# SimpleSwitchPirLightCO2Orig.net
KiCad netlist of a schematic drawn in EAGLE
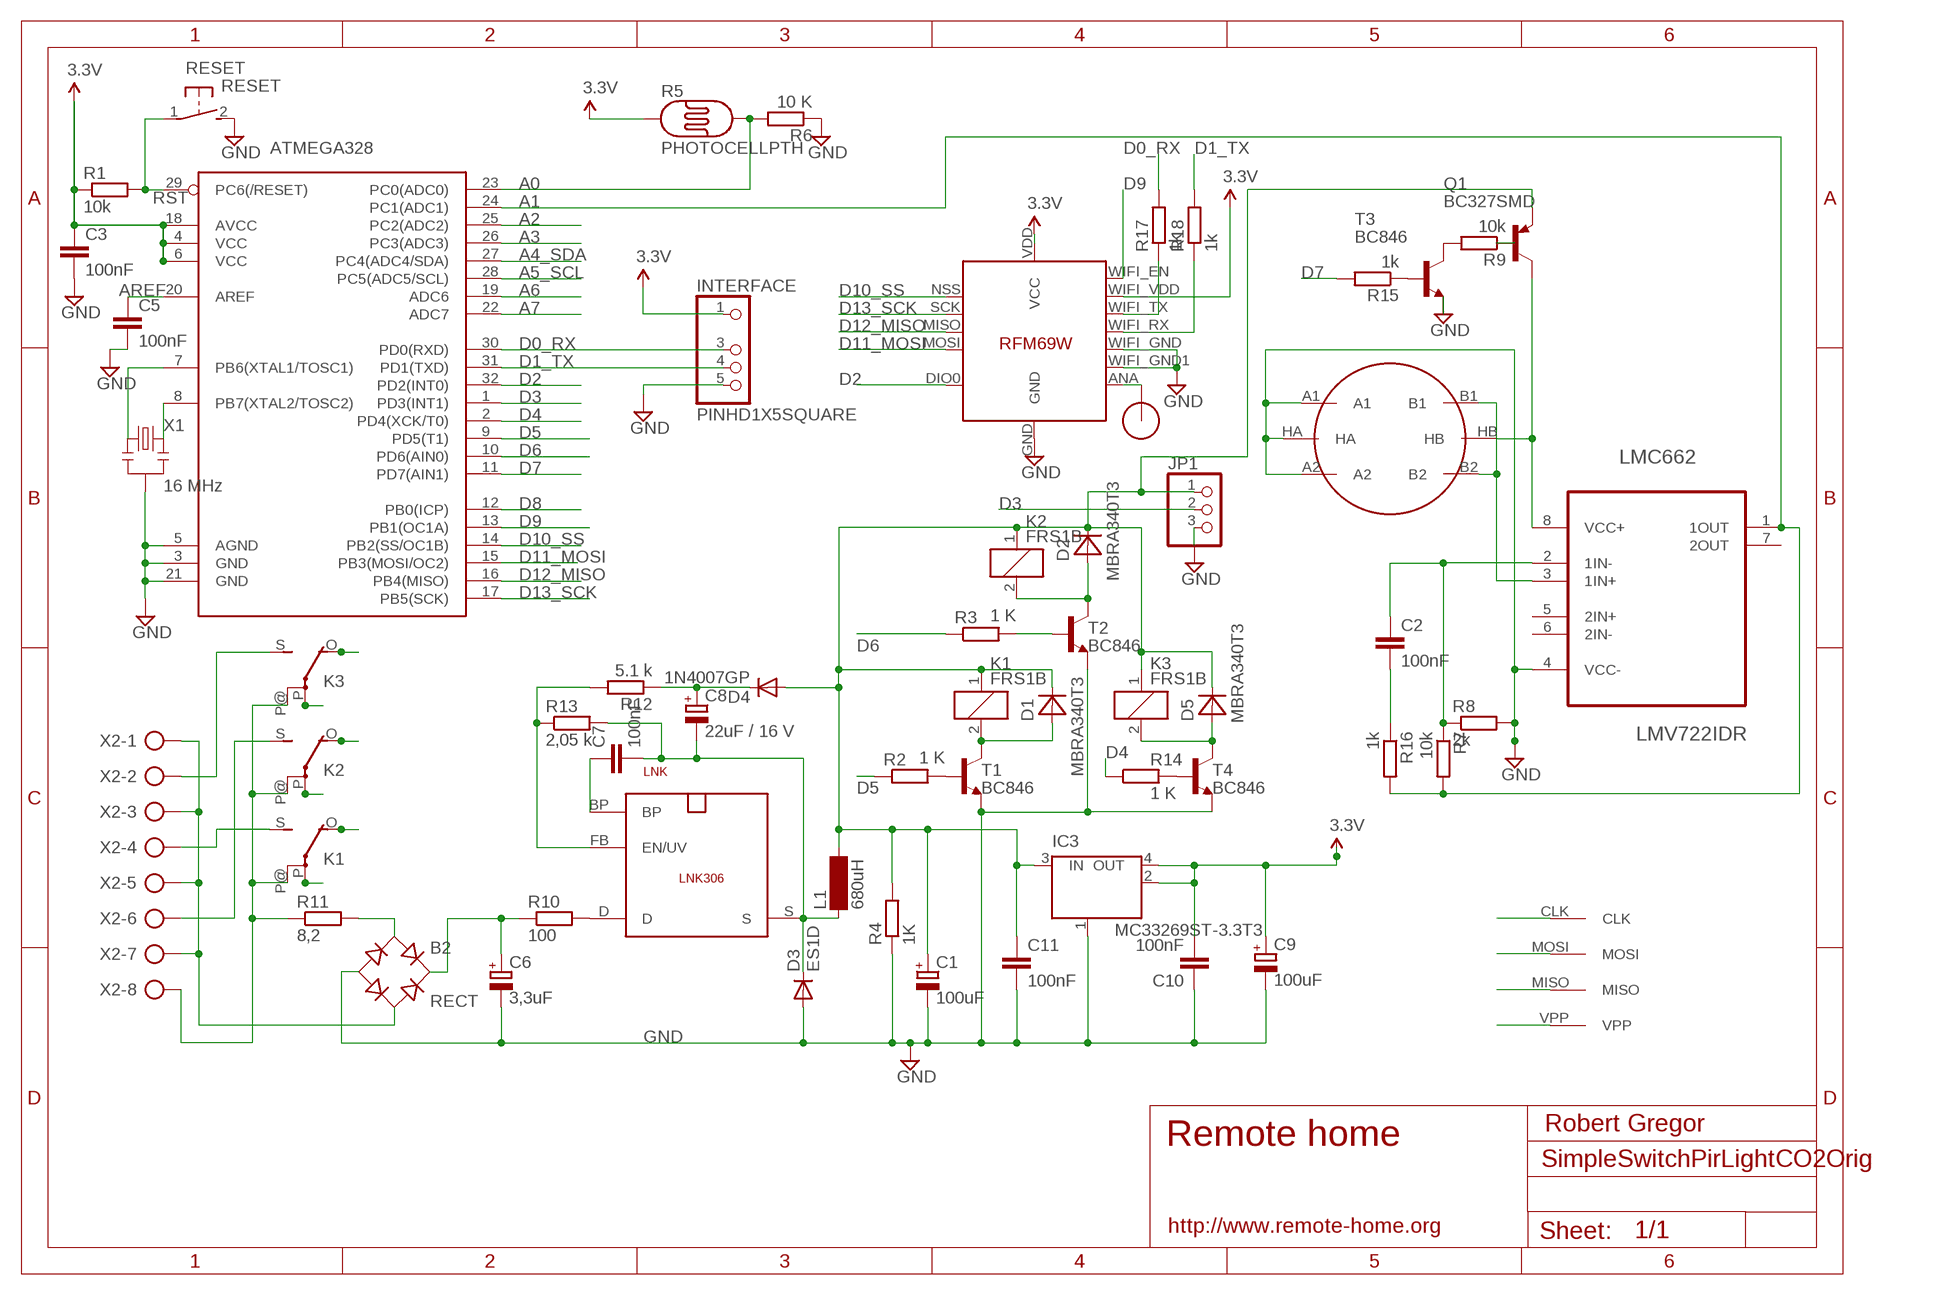
[diagram p0: schematic, sheet 1]

(export (version "E")
  (design (tool "Eeschema 10.0.6"))
  (components
    (comp (ref "ATMEGA328")
      (value "ATMega-328")
      (footprint "eagle-import:TQFP32-08")
      (libsource (lib "eagle-import") (part "ATMEGA168/328TQFP32"))
    )
    (comp (ref "B2")
      (value "RECT")
      (footprint "eagle-import:TO-269AA")
      (libsource (lib "eagle-import") (part "RECTIFIER-S40"))
    )
    (comp (ref "C1")
      (value "100uF")
      (footprint "eagle-import:SMC_B")
      (libsource (lib "eagle-import") (part "CPOL-EUSMCB"))
    )
    (comp (ref "C2")
      (value "100nF")
      (footprint "eagle-import:C2012")
      (libsource (lib "eagle-import") (part "C-EUC2012"))
    )
    (comp (ref "C3")
      (value "100nF")
      (footprint "eagle-import:C2012")
      (libsource (lib "eagle-import") (part "C-EUC2012"))
    )
    (comp (ref "C5")
      (value "100nF")
      (footprint "eagle-import:C2012")
      (libsource (lib "eagle-import") (part "C-EUC2012"))
    )
    (comp (ref "C6")
      (value "3,3uF")
      (footprint "eagle-import:E5-10,5")
      (libsource (lib "eagle-import") (part "CPOL-EUE5-10.5"))
    )
    (comp (ref "C7")
      (value "100nF")
      (footprint "eagle-import:C2012")
      (libsource (lib "eagle-import") (part "C-EUC2012"))
    )
    (comp (ref "C8")
      (value "22uF / 16 V")
      (footprint "eagle-import:SMC_C")
      (libsource (lib "eagle-import") (part "CPOL-EUSMCC"))
    )
    (comp (ref "C9")
      (value "100uF")
      (footprint "eagle-import:SMC_B")
      (libsource (lib "eagle-import") (part "CPOL-EUSMCB"))
    )
    (comp (ref "C10")
      (value "100nF")
      (footprint "eagle-import:C2012")
      (libsource (lib "eagle-import") (part "C-EUC2012"))
    )
    (comp (ref "C11")
      (value "100nF")
      (footprint "eagle-import:C2012")
      (libsource (lib "eagle-import") (part "C-EUC2012"))
    )
    (comp (ref "D1")
      (value "MBRA340T3")
      (footprint "eagle-import:SMA")
      (libsource (lib "eagle-import") (part "MBRA340T3"))
    )
    (comp (ref "D2")
      (value "MBRA340T3")
      (footprint "eagle-import:SMA")
      (libsource (lib "eagle-import") (part "MBRA340T3"))
    )
    (comp (ref "D3")
      (value "ES1D")
      (footprint "eagle-import:DO214AC")
      (libsource (lib "eagle-import") (part "DIODE-DO214AC"))
    )
    (comp (ref "D4")
      (value "1N4007GP")
      (footprint "eagle-import:DO214AA")
      (libsource (lib "eagle-import") (part "DIODE-DO214AA"))
    )
    (comp (ref "D5")
      (value "MBRA340T3")
      (footprint "eagle-import:SMA")
      (libsource (lib "eagle-import") (part "MBRA340T3"))
    )
    (comp (ref "IC3")
      (value "MC33269ST-3.3T3")
      (footprint "eagle-import:SOT223")
      (libsource (lib "eagle-import") (part "MC33269ST-3.3T3"))
    )
    (comp (ref "INTERFACE")
      (value "PINHD1X5SQUARE")
      (footprint "eagle-import:PINHD1X05-SQUARE")
      (libsource (lib "eagle-import") (part "PINHD1X5SQUARE"))
    )
    (comp (ref "JP1")
      (value "PINHD-1X03_2.54-S")
      (footprint "eagle-import:1X03-S")
      (libsource (lib "eagle-import") (part "PINHD-1X03_2.54-S"))
    )
    (comp (ref "K1")
      (value "FRS1B")
      (footprint "eagle-import:FRS1B")
      (libsource (lib "eagle-import") (part "FRS1B"))
    )
    (comp (ref "K2")
      (value "FRS1B")
      (footprint "eagle-import:FRS1B")
      (libsource (lib "eagle-import") (part "FRS1B"))
    )
    (comp (ref "K3")
      (value "FRS1B")
      (footprint "eagle-import:FRS1B")
      (libsource (lib "eagle-import") (part "FRS1B"))
    )
    (comp (ref "L1")
      (value "680uH")
      (footprint "eagle-import:BS11")
      (libsource (lib "eagle-import") (part "BS11"))
    )
    (comp (ref "LMC662")
      (value "LMV722IDR")
      (footprint "eagle-import:SOIC127P600X175-8N")
      (libsource (lib "eagle-import") (part "LMV722IDR"))
    )
    (comp (ref "LNK")
      (value "LNK306")
      (footprint "eagle-import:SO-8C")
      (libsource (lib "eagle-import") (part "SO-8C"))
    )
    (comp (ref "Q1")
      (value "BC327SMD")
      (footprint "eagle-import:SOT23-BEC")
      (libsource (lib "eagle-import") (part "BC327SMD"))
    )
    (comp (ref "R1")
      (value "10k")
      (footprint "eagle-import:R2012")
      (libsource (lib "eagle-import") (part "R-EU_R2012"))
    )
    (comp (ref "R2")
      (value "1 K")
      (footprint "eagle-import:M2012")
      (libsource (lib "eagle-import") (part "R-EU_M2012"))
    )
    (comp (ref "R3")
      (value "1 K")
      (footprint "eagle-import:M2012")
      (libsource (lib "eagle-import") (part "R-EU_M2012"))
    )
    (comp (ref "R4")
      (value "1K")
      (footprint "eagle-import:M2012")
      (libsource (lib "eagle-import") (part "R-EU_M2012"))
    )
    (comp (ref "R5")
      (value "PHOTOCELLPTH")
      (footprint "eagle-import:PHOTOCELL")
      (libsource (lib "eagle-import") (part "PHOTOCELLPTH"))
    )
    (comp (ref "R6")
      (value "10 K")
      (footprint "eagle-import:M2012")
      (libsource (lib "eagle-import") (part "R-EU_M2012"))
    )
    (comp (ref "R7")
      (value "10k")
      (footprint "eagle-import:R2012")
      (libsource (lib "eagle-import") (part "R-EU_R2012"))
    )
    (comp (ref "R8")
      (value "2k")
      (footprint "eagle-import:R2012")
      (libsource (lib "eagle-import") (part "R-EU_R2012"))
    )
    (comp (ref "R9")
      (value "10k")
      (footprint "eagle-import:R2012")
      (libsource (lib "eagle-import") (part "R-EU_R2012"))
    )
    (comp (ref "R10")
      (value "100")
      (footprint "eagle-import:R2512W")
      (libsource (lib "eagle-import") (part "R-EU_R2512W"))
    )
    (comp (ref "R11")
      (value "8,2")
      (footprint "eagle-import:0411_12")
      (libsource (lib "eagle-import") (part "R-EU_0411/12"))
    )
    (comp (ref "R12")
      (value "5.1 k")
      (footprint "eagle-import:M2012")
      (libsource (lib "eagle-import") (part "R-EU_M2012"))
    )
    (comp (ref "R13")
      (value "2,05 k")
      (footprint "eagle-import:M2012")
      (libsource (lib "eagle-import") (part "R-EU_M2012"))
    )
    (comp (ref "R14")
      (value "1 K")
      (footprint "eagle-import:M2012")
      (libsource (lib "eagle-import") (part "R-EU_M2012"))
    )
    (comp (ref "R15")
      (value "1k")
      (footprint "eagle-import:R2012")
      (libsource (lib "eagle-import") (part "R-EU_R2012"))
    )
    (comp (ref "R16")
      (value "1k")
      (footprint "eagle-import:R2012")
      (libsource (lib "eagle-import") (part "R-EU_R2012"))
    )
    (comp (ref "R17")
      (value "1k")
      (footprint "eagle-import:R2012")
      (libsource (lib "eagle-import") (part "R-EU_R2012"))
    )
    (comp (ref "R18")
      (value "1k")
      (footprint "eagle-import:R2012")
      (libsource (lib "eagle-import") (part "R-EU_R2012"))
    )
    (comp (ref "RESET")
      (value "RESET")
      (footprint "eagle-import:DTSM-3")
      (libsource (lib "eagle-import") (part "DTSM-3"))
    )
    (comp (ref "RFM69")
      (value "RFM69-ESP03")
      (footprint "eagle-import:RFM69W-ESP03")
      (libsource (lib "eagle-import") (part "RFM69-ESP03"))
    )
    (comp (ref "T1")
      (value "BC846")
      (footprint "eagle-import:SOT23")
      (libsource (lib "eagle-import") (part "BC846"))
    )
    (comp (ref "T2")
      (value "BC846")
      (footprint "eagle-import:SOT23")
      (libsource (lib "eagle-import") (part "BC846"))
    )
    (comp (ref "T3")
      (value "BC846")
      (footprint "eagle-import:SOT23")
      (libsource (lib "eagle-import") (part "BC846"))
    )
    (comp (ref "T4")
      (value "BC846")
      (footprint "eagle-import:SOT23")
      (libsource (lib "eagle-import") (part "BC846"))
    )
    (comp (ref "U$1")
      (value "RFM12B_ANTENNA")
      (footprint "eagle-import:RFM12B-ANTENNA")
      (libsource (lib "eagle-import") (part "RFM12B_ANTENNA"))
    )
    (comp (ref "U$2")
      (value "AVRHEADERDIP")
      (footprint "eagle-import:AVRHEADER")
      (libsource (lib "eagle-import") (part "AVRHEADERDIP"))
    )
    (comp (ref "U$4")
      (value "METHANE_SENSOR")
      (footprint "eagle-import:MQ-3")
      (libsource (lib "eagle-import") (part "METHANE_SENSOR"))
    )
    (comp (ref "X1")
      (value "16 MHz")
      (footprint "eagle-import:RESONATOR-SMD")
      (libsource (lib "eagle-import") (part "RESONATORSMD"))
    )
    (comp (ref "X2")
      (value "AK500/8")
      (footprint "eagle-import:AK500_8")
      (libsource (lib "eagle-import") (part "AK500/8"))
    )
  )
  (nets
    (net (code "1") (name "/A0") (class "Default")
      (node (ref "ATMEGA328") (pin "23") (pinfunction "PC0(ADC0)_23") (pintype "bidirectional"))
      (node (ref "R5") (pin "2") (pinfunction "P$2_2") (pintype "bidirectional"))
      (node (ref "R6") (pin "2") (pinfunction "2_2") (pintype "passive"))
    )
    (net (code "2") (name "/A1") (class "Default")
      (node (ref "ATMEGA328") (pin "24") (pinfunction "PC1(ADC1)_24") (pintype "bidirectional"))
      (node (ref "LMC662") (pin "1") (pinfunction "1OUT_1") (pintype "output"))
      (node (ref "R16") (pin "2") (pinfunction "2_2") (pintype "passive"))
      (node (ref "R7") (pin "2") (pinfunction "2_2") (pintype "passive"))
    )
    (net (code "3") (name "/A2") (class "Default")
      (node (ref "ATMEGA328") (pin "25") (pinfunction "PC2(ADC2)_25") (pintype "bidirectional"))
    )
    (net (code "4") (name "/A3") (class "Default")
      (node (ref "ATMEGA328") (pin "26") (pinfunction "PC3(ADC3)_26") (pintype "bidirectional"))
    )
    (net (code "5") (name "/A4_SDA") (class "Default")
      (node (ref "ATMEGA328") (pin "27") (pinfunction "PC4(ADC4/SDA)_27") (pintype "bidirectional"))
    )
    (net (code "6") (name "/A5_SCL") (class "Default")
      (node (ref "ATMEGA328") (pin "28") (pinfunction "PC5(ADC5/SCL)_28") (pintype "bidirectional"))
    )
    (net (code "7") (name "/A6") (class "Default")
      (node (ref "ATMEGA328") (pin "19") (pinfunction "ADC6_19") (pintype "bidirectional"))
    )
    (net (code "8") (name "/A7") (class "Default")
      (node (ref "ATMEGA328") (pin "22") (pinfunction "ADC7_22") (pintype "bidirectional"))
    )
    (net (code "9") (name "/AREF") (class "Default")
      (node (ref "ATMEGA328") (pin "20") (pinfunction "AREF_20") (pintype "bidirectional"))
      (node (ref "C5") (pin "1") (pinfunction "1_1") (pintype "passive"))
    )
    (net (code "10") (name "/D0_RX") (class "Default")
      (node (ref "ATMEGA328") (pin "30") (pinfunction "PD0(RXD)_30") (pintype "bidirectional"))
      (node (ref "INTERFACE") (pin "3") (pinfunction "3_3") (pintype "passive"))
      (node (ref "R17") (pin "2") (pinfunction "2_2") (pintype "passive"))
    )
    (net (code "11") (name "/D1_TX") (class "Default")
      (node (ref "ATMEGA328") (pin "31") (pinfunction "PD1(TXD)_31") (pintype "bidirectional"))
      (node (ref "INTERFACE") (pin "4") (pinfunction "4_4") (pintype "passive"))
      (node (ref "R18") (pin "2") (pinfunction "2_2") (pintype "passive"))
    )
    (net (code "12") (name "/D2") (class "Default")
      (node (ref "ATMEGA328") (pin "32") (pinfunction "PD2(INT0)_32") (pintype "bidirectional"))
      (node (ref "RFM69") (pin "DIO0") (pinfunction "DIO0_DIO0") (pintype "open_collector"))
    )
    (net (code "13") (name "/D3") (class "Default")
      (node (ref "ATMEGA328") (pin "1") (pinfunction "PD3(INT1)_1") (pintype "bidirectional"))
      (node (ref "JP1") (pin "2") (pinfunction "2_2") (pintype "passive"))
    )
    (net (code "14") (name "/D4") (class "Default")
      (node (ref "ATMEGA328") (pin "2") (pinfunction "PD4(XCK/T0)_2") (pintype "bidirectional"))
      (node (ref "R14") (pin "1") (pinfunction "1_1") (pintype "passive"))
    )
    (net (code "15") (name "/D5") (class "Default")
      (node (ref "ATMEGA328") (pin "9") (pinfunction "PD5(T1)_9") (pintype "bidirectional"))
      (node (ref "R2") (pin "1") (pinfunction "1_1") (pintype "passive"))
    )
    (net (code "16") (name "/D6") (class "Default")
      (node (ref "ATMEGA328") (pin "10") (pinfunction "PD6(AIN0)_10") (pintype "bidirectional"))
      (node (ref "R3") (pin "1") (pinfunction "1_1") (pintype "passive"))
    )
    (net (code "17") (name "/D7") (class "Default")
      (node (ref "ATMEGA328") (pin "11") (pinfunction "PD7(AIN1)_11") (pintype "bidirectional"))
      (node (ref "R15") (pin "2") (pinfunction "2_2") (pintype "passive"))
    )
    (net (code "18") (name "/D8") (class "Default")
      (node (ref "ATMEGA328") (pin "12") (pinfunction "PB0(ICP)_12") (pintype "bidirectional"))
    )
    (net (code "19") (name "/D9") (class "Default")
      (node (ref "ATMEGA328") (pin "13") (pinfunction "PB1(OC1A)_13") (pintype "bidirectional"))
      (node (ref "RFM69") (pin "WIFI_EN") (pinfunction "WIFI_EN_WIFI_EN") (pintype "input"))
    )
    (net (code "20") (name "/D10_SS") (class "Default")
      (node (ref "ATMEGA328") (pin "14") (pinfunction "PB2(SS/OC1B)_14") (pintype "bidirectional"))
      (node (ref "RFM69") (pin "NSS") (pinfunction "SEL_NSS") (pintype "input"))
    )
    (net (code "21") (name "/D11_MOSI") (class "Default")
      (node (ref "ATMEGA328") (pin "15") (pinfunction "PB3(MOSI/OC2)_15") (pintype "bidirectional"))
      (node (ref "RFM69") (pin "MOSI") (pinfunction "MOSI_MOSI") (pintype "output"))
      (node (ref "U$2") (pin "MOSI") (pinfunction "MOSI_MOSI") (pintype "bidirectional"))
    )
    (net (code "22") (name "/D12_MISO") (class "Default")
      (node (ref "ATMEGA328") (pin "16") (pinfunction "PB4(MISO)_16") (pintype "bidirectional"))
      (node (ref "RFM69") (pin "MISO") (pinfunction "MISO_MISO") (pintype "input"))
      (node (ref "U$2") (pin "MISO") (pinfunction "MISO_MISO") (pintype "bidirectional"))
    )
    (net (code "23") (name "/D13_SCK") (class "Default")
      (node (ref "ATMEGA328") (pin "17") (pinfunction "PB5(SCK)_17") (pintype "bidirectional"))
      (node (ref "RFM69") (pin "SCK") (pinfunction "SCK_SCK") (pintype "input"))
      (node (ref "U$2") (pin "CLK") (pinfunction "CLK_CLK") (pintype "bidirectional"))
    )
    (net (code "24") (name "/RST") (class "Default")
      (node (ref "ATMEGA328") (pin "29") (pinfunction "PC6(/RESET)_29") (pintype "bidirectional"))
      (node (ref "R1") (pin "2") (pinfunction "2_2") (pintype "passive"))
      (node (ref "RESET") (pin "1") (pinfunction "1_1") (pintype "passive"))
      (node (ref "U$2") (pin "VPP") (pinfunction "VPP_VPP") (pintype "bidirectional"))
    )
    (net (code "25") (name "3.3V") (class "Default")
      (node (ref "ATMEGA328") (pin "18") (pinfunction "AVCC_18") (pintype "bidirectional"))
      (node (ref "ATMEGA328") (pin "4") (pinfunction "VCC_4") (pintype "bidirectional"))
      (node (ref "ATMEGA328") (pin "6") (pinfunction "VCC_6") (pintype "bidirectional"))
      (node (ref "C10") (pin "2") (pinfunction "2_2") (pintype "passive"))
      (node (ref "C3") (pin "1") (pinfunction "1_1") (pintype "passive"))
      (node (ref "C9") (pin "+") (pinfunction "+_+") (pintype "passive"))
      (node (ref "IC3") (pin "2") (pinfunction "OUT_2") (pintype "passive"))
      (node (ref "IC3") (pin "4") (pinfunction "OUT_4") (pintype "passive"))
      (node (ref "INTERFACE") (pin "1") (pinfunction "1_1") (pintype "passive"))
      (node (ref "R1") (pin "1") (pinfunction "1_1") (pintype "passive"))
      (node (ref "R5") (pin "1") (pinfunction "P$1_1") (pintype "bidirectional"))
      (node (ref "RFM69") (pin "VDD") (pinfunction "VCC_VDD") (pintype "power_in"))
      (node (ref "RFM69") (pin "WIFI_VDD") (pinfunction "WIFI_VDD_WIFI_VDD") (pintype "input"))
    )
    (net (code "26") (name "GND") (class "Default")
      (node (ref "ATMEGA328") (pin "21") (pinfunction "GND_21") (pintype "bidirectional"))
      (node (ref "ATMEGA328") (pin "3") (pinfunction "GND_3") (pintype "bidirectional"))
      (node (ref "ATMEGA328") (pin "5") (pinfunction "AGND_5") (pintype "bidirectional"))
      (node (ref "B2") (pin "-") (pinfunction "-_-") (pintype "passive"))
      (node (ref "C1") (pin "-") (pinfunction "-_-") (pintype "passive"))
      (node (ref "C10") (pin "1") (pinfunction "1_1") (pintype "passive"))
      (node (ref "C11") (pin "2") (pinfunction "2_2") (pintype "passive"))
      (node (ref "C3") (pin "2") (pinfunction "2_2") (pintype "passive"))
      (node (ref "C5") (pin "2") (pinfunction "2_2") (pintype "passive"))
      (node (ref "C6") (pin "-") (pinfunction "-_-") (pintype "passive"))
      (node (ref "C9") (pin "-") (pinfunction "-_-") (pintype "passive"))
      (node (ref "D3") (pin "A") (pinfunction "A_A") (pintype "passive"))
      (node (ref "IC3") (pin "1") (pinfunction "GND/ADJ_1") (pintype "input"))
      (node (ref "INTERFACE") (pin "5") (pinfunction "5_5") (pintype "passive"))
      (node (ref "JP1") (pin "3") (pinfunction "3_3") (pintype "passive"))
      (node (ref "LMC662") (pin "4") (pinfunction "VCC-_4") (pintype "power_in"))
      (node (ref "R4") (pin "1") (pinfunction "1_1") (pintype "passive"))
      (node (ref "R6") (pin "1") (pinfunction "1_1") (pintype "passive"))
      (node (ref "R8") (pin "2") (pinfunction "2_2") (pintype "passive"))
      (node (ref "RESET") (pin "2") (pinfunction "2_2") (pintype "passive"))
      (node (ref "RFM69") (pin "GND") (pinfunction "GND_GND") (pintype "power_in"))
      (node (ref "RFM69") (pin "WIFI_GND") (pinfunction "WIFI_GND_WIFI_GND") (pintype "input"))
      (node (ref "RFM69") (pin "WIFI_GND1") (pinfunction "WIFI_GND1_WIFI_GND1") (pintype "input"))
      (node (ref "T1") (pin "2") (pinfunction "E_2") (pintype "passive"))
      (node (ref "T2") (pin "2") (pinfunction "E_2") (pintype "passive"))
      (node (ref "T3") (pin "2") (pinfunction "E_2") (pintype "passive"))
      (node (ref "T4") (pin "2") (pinfunction "E_2") (pintype "passive"))
      (node (ref "U$4") (pin "A1") (pinfunction "A1_A1") (pintype "bidirectional"))
      (node (ref "U$4") (pin "A2") (pinfunction "A2_A2") (pintype "bidirectional"))
      (node (ref "U$4") (pin "HA") (pinfunction "HA_HA") (pintype "bidirectional"))
      (node (ref "X1") (pin "2") (pinfunction "2_2") (pintype "passive"))
    )
    (net (code "27") (name "Net-(ATMEGA328-PB6(XTAL1{slash}TOSC1))") (class "Default")
      (node (ref "ATMEGA328") (pin "7") (pinfunction "PB6(XTAL1/TOSC1)_7") (pintype "bidirectional"))
      (node (ref "X1") (pin "1") (pinfunction "1_1") (pintype "passive"))
    )
    (net (code "28") (name "Net-(ATMEGA328-PB7(XTAL2{slash}TOSC2))") (class "Default")
      (node (ref "ATMEGA328") (pin "8") (pinfunction "PB7(XTAL2/TOSC2)_8") (pintype "bidirectional"))
      (node (ref "X1") (pin "3") (pinfunction "3_3") (pintype "passive"))
    )
    (net (code "29") (name "Net-(B2-Pad+)") (class "Default")
      (node (ref "B2") (pin "+") (pinfunction "+_+") (pintype "passive"))
      (node (ref "C6") (pin "+") (pinfunction "+_+") (pintype "passive"))
      (node (ref "R10") (pin "1") (pinfunction "1_1") (pintype "passive"))
    )
    (net (code "30") (name "Net-(B2-PadAC1)") (class "Default")
      (node (ref "B2") (pin "AC1") (pinfunction "AC1_AC1") (pintype "passive"))
      (node (ref "R11") (pin "2") (pinfunction "2_2") (pintype "passive"))
    )
    (net (code "31") (name "Net-(C2-Pad2)") (class "Default")
      (node (ref "C2") (pin "2") (pinfunction "2_2") (pintype "passive"))
      (node (ref "R16") (pin "1") (pinfunction "1_1") (pintype "passive"))
    )
    (net (code "32") (name "Net-(C7-Pad1)") (class "Default")
      (node (ref "C7") (pin "1") (pinfunction "1_1") (pintype "passive"))
      (node (ref "LNK") (pin "BP") (pinfunction "BP_BP") (pintype "passive"))
    )
    (net (code "33") (name "Net-(C7-Pad2)") (class "Default")
      (node (ref "C7") (pin "2") (pinfunction "2_2") (pintype "passive"))
      (node (ref "C8") (pin "-") (pinfunction "-_-") (pintype "passive"))
      (node (ref "D3") (pin "C") (pinfunction "C_C") (pintype "passive"))
      (node (ref "L1") (pin "1") (pinfunction "1_1") (pintype "passive"))
      (node (ref "LNK") (pin "S") (pinfunction "S_S") (pintype "power_in"))
      (node (ref "R13") (pin "2") (pinfunction "2_2") (pintype "passive"))
    )
    (net (code "34") (name "Net-(C8-Pad+)") (class "Default")
      (node (ref "C8") (pin "+") (pinfunction "+_+") (pintype "passive"))
      (node (ref "D4") (pin "C") (pinfunction "C_C") (pintype "passive"))
      (node (ref "R12") (pin "1") (pinfunction "1_1") (pintype "passive"))
    )
    (net (code "35") (name "Net-(IC3-IN)") (class "Default")
      (node (ref "C1") (pin "+") (pinfunction "+_+") (pintype "passive"))
      (node (ref "C11") (pin "1") (pinfunction "1_1") (pintype "passive"))
      (node (ref "D1") (pin "C") (pinfunction "C_C") (pintype "passive"))
      (node (ref "D2") (pin "C") (pinfunction "C_C") (pintype "passive"))
      (node (ref "D4") (pin "A") (pinfunction "A_A") (pintype "passive"))
      (node (ref "D5") (pin "C") (pinfunction "C_C") (pintype "passive"))
      (node (ref "IC3") (pin "3") (pinfunction "IN_3") (pintype "input"))
      (node (ref "JP1") (pin "1") (pinfunction "1_1") (pintype "passive"))
      (node (ref "K1") (pin "1") (pinfunction "1_1") (pintype "passive"))
      (node (ref "K2") (pin "1") (pinfunction "1_1") (pintype "passive"))
      (node (ref "K3") (pin "1") (pinfunction "1_1") (pintype "passive"))
      (node (ref "L1") (pin "2") (pinfunction "2_2") (pintype "passive"))
      (node (ref "Q1") (pin "E") (pinfunction "E_E") (pintype "passive"))
      (node (ref "R4") (pin "2") (pinfunction "2_2") (pintype "passive"))
    )
    (net (code "36") (name "Net-(LMC662-1IN+)") (class "Default")
      (node (ref "LMC662") (pin "3") (pinfunction "1IN+_3") (pintype "input"))
      (node (ref "U$4") (pin "B1") (pinfunction "B1_B1") (pintype "bidirectional"))
      (node (ref "U$4") (pin "B2") (pinfunction "B2_B2") (pintype "bidirectional"))
    )
    (net (code "37") (name "Net-(LMC662-1IN-)") (class "Default")
      (node (ref "C2") (pin "1") (pinfunction "1_1") (pintype "passive"))
      (node (ref "LMC662") (pin "2") (pinfunction "1IN-_2") (pintype "input"))
      (node (ref "R7") (pin "1") (pinfunction "1_1") (pintype "passive"))
      (node (ref "R8") (pin "1") (pinfunction "1_1") (pintype "passive"))
    )
    (net (code "38") (name "Net-(LMC662-VCC+)") (class "Default")
      (node (ref "LMC662") (pin "8") (pinfunction "VCC+_8") (pintype "power_in"))
      (node (ref "Q1") (pin "C") (pinfunction "C_C") (pintype "passive"))
      (node (ref "U$4") (pin "HB") (pinfunction "HB_HB") (pintype "bidirectional"))
    )
    (net (code "39") (name "Net-(LNK-EN{slash}UV)") (class "Default")
      (node (ref "LNK") (pin "FB") (pinfunction "EN/UV_FB") (pintype "input"))
      (node (ref "R12") (pin "2") (pinfunction "2_2") (pintype "passive"))
      (node (ref "R13") (pin "1") (pinfunction "1_1") (pintype "passive"))
    )
    (net (code "40") (name "Net-(LNK-PadD)") (class "Default")
      (node (ref "LNK") (pin "D") (pinfunction "D_D") (pintype "open_collector"))
      (node (ref "R10") (pin "2") (pinfunction "2_2") (pintype "passive"))
    )
    (net (code "41") (name "Net-(Q1-PadB)") (class "Default")
      (node (ref "Q1") (pin "B") (pinfunction "B_B") (pintype "passive"))
      (node (ref "R9") (pin "1") (pinfunction "1_1") (pintype "passive"))
    )
    (net (code "42") (name "Net-(R17-Pad1)") (class "Default")
      (node (ref "R17") (pin "1") (pinfunction "1_1") (pintype "passive"))
      (node (ref "RFM69") (pin "WIFI_TX") (pinfunction "WIFI_TX_WIFI_TX") (pintype "input"))
    )
    (net (code "43") (name "Net-(R18-Pad1)") (class "Default")
      (node (ref "R18") (pin "1") (pinfunction "1_1") (pintype "passive"))
      (node (ref "RFM69") (pin "WIFI_RX") (pinfunction "WIFI_RX_WIFI_RX") (pintype "input"))
    )
    (net (code "44") (name "Net-(RFM69-ANT)") (class "Default")
      (node (ref "RFM69") (pin "ANA") (pinfunction "ANT_ANA") (pintype "passive"))
      (node (ref "U$1") (pin "P$1") (pinfunction "1_P$1") (pintype "bidirectional"))
    )
    (net (code "45") (name "Net-(T1-B)") (class "Default")
      (node (ref "R2") (pin "2") (pinfunction "2_2") (pintype "passive"))
      (node (ref "T1") (pin "1") (pinfunction "B_1") (pintype "passive"))
    )
    (net (code "46") (name "Net-(T1-C)") (class "Default")
      (node (ref "D1") (pin "A") (pinfunction "A_A") (pintype "passive"))
      (node (ref "K1") (pin "2") (pinfunction "2_2") (pintype "passive"))
      (node (ref "T1") (pin "3") (pinfunction "C_3") (pintype "passive"))
    )
    (net (code "47") (name "Net-(T2-B)") (class "Default")
      (node (ref "R3") (pin "2") (pinfunction "2_2") (pintype "passive"))
      (node (ref "T2") (pin "1") (pinfunction "B_1") (pintype "passive"))
    )
    (net (code "48") (name "Net-(T2-C)") (class "Default")
      (node (ref "D2") (pin "A") (pinfunction "A_A") (pintype "passive"))
      (node (ref "K2") (pin "2") (pinfunction "2_2") (pintype "passive"))
      (node (ref "T2") (pin "3") (pinfunction "C_3") (pintype "passive"))
    )
    (net (code "49") (name "Net-(T3-B)") (class "Default")
      (node (ref "R15") (pin "1") (pinfunction "1_1") (pintype "passive"))
      (node (ref "T3") (pin "1") (pinfunction "B_1") (pintype "passive"))
    )
    (net (code "50") (name "Net-(T3-C)") (class "Default")
      (node (ref "R9") (pin "2") (pinfunction "2_2") (pintype "passive"))
      (node (ref "T3") (pin "3") (pinfunction "C_3") (pintype "passive"))
    )
    (net (code "51") (name "Net-(T4-B)") (class "Default")
      (node (ref "R14") (pin "2") (pinfunction "2_2") (pintype "passive"))
      (node (ref "T4") (pin "1") (pinfunction "B_1") (pintype "passive"))
    )
    (net (code "52") (name "Net-(T4-C)") (class "Default")
      (node (ref "D5") (pin "A") (pinfunction "A_A") (pintype "passive"))
      (node (ref "K3") (pin "2") (pinfunction "2_2") (pintype "passive"))
      (node (ref "T4") (pin "3") (pinfunction "C_3") (pintype "passive"))
    )
    (net (code "53") (name "Net-(X2A-KL)") (class "Default")
      (node (ref "B2") (pin "AC2") (pinfunction "AC2_AC2") (pintype "passive"))
      (node (ref "X2") (pin "1") (pinfunction "KL_1") (pintype "passive"))
      (node (ref "X2") (pin "3") (pinfunction "KL_3") (pintype "passive"))
      (node (ref "X2") (pin "5") (pinfunction "KL_5") (pintype "passive"))
      (node (ref "X2") (pin "7") (pinfunction "KL_7") (pintype "passive"))
    )
    (net (code "54") (name "Net-(X2B-KL)") (class "Default")
      (node (ref "K3") (pin "S") (pinfunction "S_S") (pintype "passive"))
      (node (ref "X2") (pin "2") (pinfunction "KL_2") (pintype "passive"))
    )
    (net (code "55") (name "Net-(X2D-KL)") (class "Default")
      (node (ref "K1") (pin "S") (pinfunction "S_S") (pintype "passive"))
      (node (ref "X2") (pin "4") (pinfunction "KL_4") (pintype "passive"))
    )
    (net (code "56") (name "Net-(X2F-KL)") (class "Default")
      (node (ref "K2") (pin "S") (pinfunction "S_S") (pintype "passive"))
      (node (ref "X2") (pin "6") (pinfunction "KL_6") (pintype "passive"))
    )
    (net (code "57") (name "Net-(X2H-KL)") (class "Default")
      (node (ref "K1") (pin "P@") (pinfunction "P_P@") (pintype "passive"))
      (node (ref "K2") (pin "P@") (pinfunction "P_P@") (pintype "passive"))
      (node (ref "K3") (pin "P@") (pinfunction "P_P@") (pintype "passive"))
      (node (ref "R11") (pin "1") (pinfunction "1_1") (pintype "passive"))
      (node (ref "X2") (pin "8") (pinfunction "KL_8") (pintype "passive"))
    )
    (net (code "58") (name "unconnected-(K1-PadO)") (class "Default")
      (node (ref "K1") (pin "O") (pinfunction "O_O") (pintype "passive"))
    )
    (net (code "59") (name "unconnected-(K1-PadP)") (class "Default")
      (node (ref "K1") (pin "P") (pinfunction "P_P") (pintype "passive"))
    )
    (net (code "60") (name "unconnected-(K2-PadO)") (class "Default")
      (node (ref "K2") (pin "O") (pinfunction "O_O") (pintype "passive"))
    )
    (net (code "61") (name "unconnected-(K2-PadP)") (class "Default")
      (node (ref "K2") (pin "P") (pinfunction "P_P") (pintype "passive"))
    )
    (net (code "62") (name "unconnected-(K3-PadO)") (class "Default")
      (node (ref "K3") (pin "O") (pinfunction "O_O") (pintype "passive"))
    )
    (net (code "63") (name "unconnected-(K3-PadP)") (class "Default")
      (node (ref "K3") (pin "P") (pinfunction "P_P") (pintype "passive"))
    )
    (net (code "64") (name "unconnected-(LMC662-2IN+-Pad5)") (class "Default")
      (node (ref "LMC662") (pin "5") (pinfunction "2IN+_5") (pintype "input"))
    )
    (net (code "65") (name "unconnected-(LMC662-2IN--Pad6)") (class "Default")
      (node (ref "LMC662") (pin "6") (pinfunction "2IN-_6") (pintype "input"))
    )
    (net (code "66") (name "unconnected-(LMC662-2OUT-Pad7)") (class "Default")
      (node (ref "LMC662") (pin "7") (pinfunction "2OUT_7") (pintype "output"))
    )
  )
)
